# CajitaAbierta.net
KiCad netlist of a schematic drawn in EAGLE
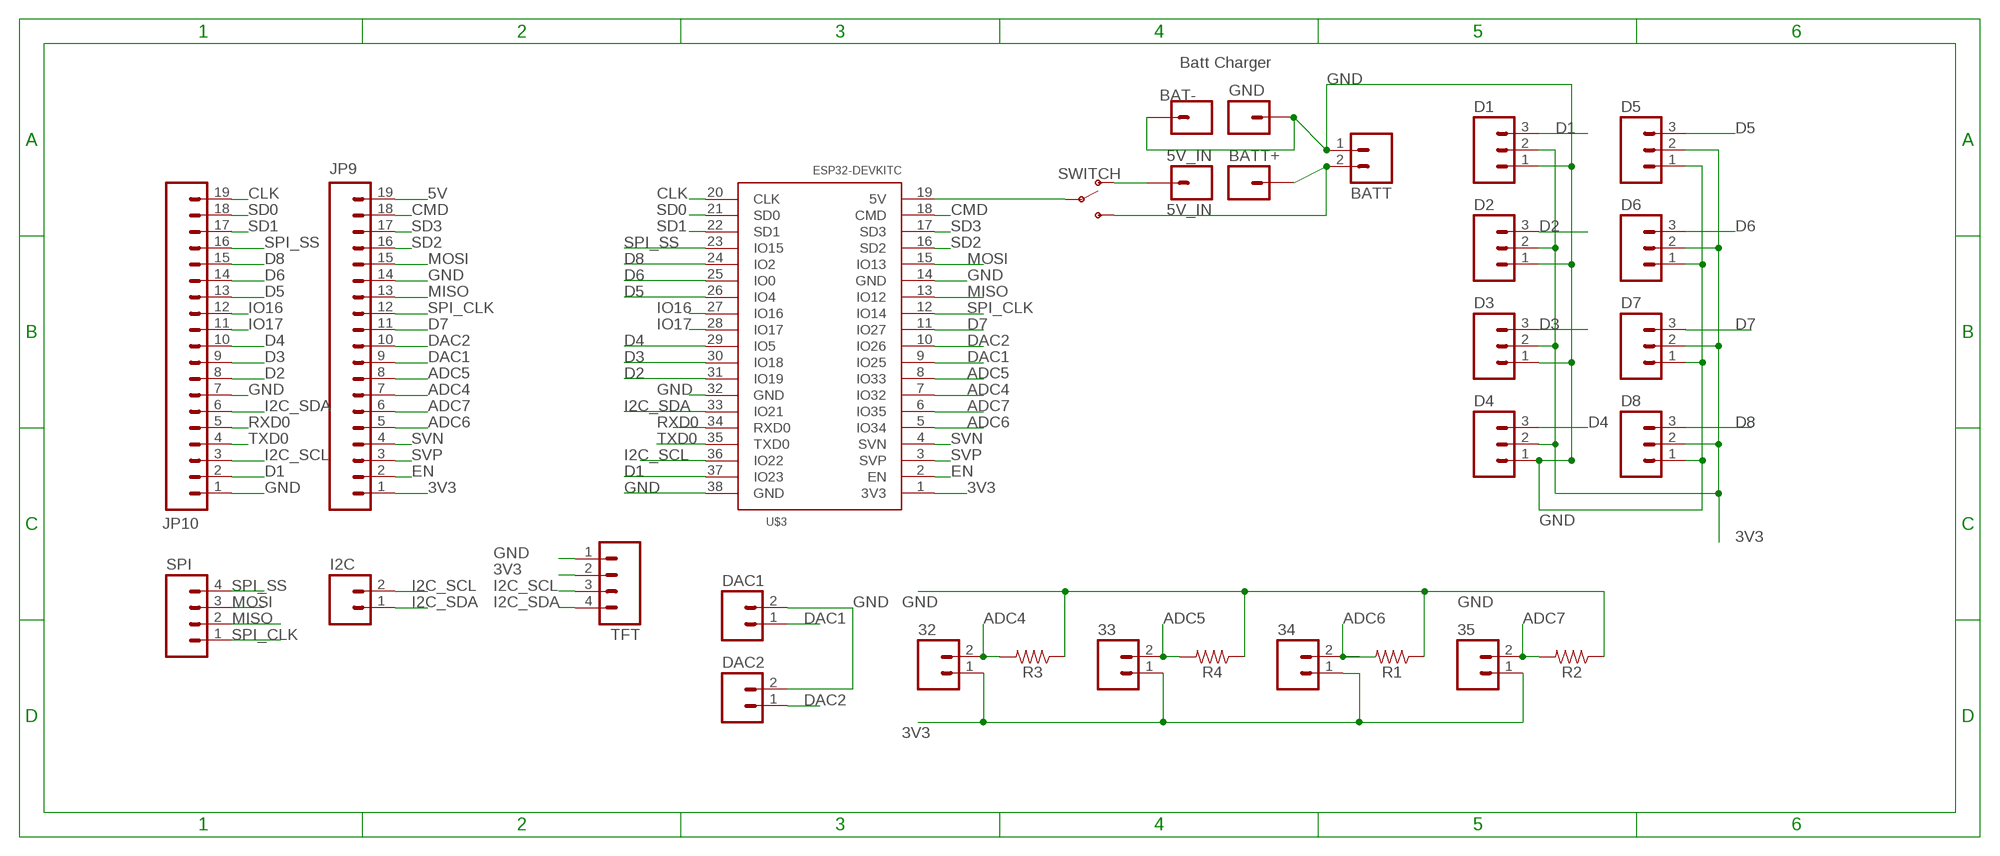
[diagram p0: schematic, sheet 1]

(export (version "E")
  (design (tool "Eeschema 10.0.6"))
  (components
    (comp (ref "5V_IN")
      (value "5V_IN")
      (footprint "eagle-import:1X01")
      (libsource (lib "eagle-import") (part "M01PTH"))
    )
    (comp (ref "32")
      (value "M02PTH")
      (footprint "eagle-import:1X02")
      (libsource (lib "eagle-import") (part "SparkFun-Connectors_6242394_M02PTH"))
    )
    (comp (ref "33")
      (value "M02PTH")
      (footprint "eagle-import:1X02")
      (libsource (lib "eagle-import") (part "SparkFun-Connectors_6242394_M02PTH"))
    )
    (comp (ref "34")
      (value "M02PTH")
      (footprint "eagle-import:1X02")
      (libsource (lib "eagle-import") (part "SparkFun-Connectors_6242394_M02PTH"))
    )
    (comp (ref "35")
      (value "M02PTH")
      (footprint "eagle-import:1X02")
      (libsource (lib "eagle-import") (part "SparkFun-Connectors_6242394_M02PTH"))
    )
    (comp (ref "BAT-")
      (value "M01PTH")
      (footprint "eagle-import:1X01")
      (libsource (lib "eagle-import") (part "M01PTH"))
    )
    (comp (ref "BATT")
      (value "M02LOCK_LONGPADS")
      (footprint "eagle-import:1X02_LOCK_LONGPADS")
      (libsource (lib "eagle-import") (part "M02LOCK_LONGPADS"))
    )
    (comp (ref "BATT+")
      (value "M01PTH")
      (footprint "eagle-import:1X01")
      (libsource (lib "eagle-import") (part "M01PTH"))
    )
    (comp (ref "D1")
      (value "M03LOCK_LONGPADS")
      (footprint "eagle-import:1X03_LOCK_LONGPADS")
      (libsource (lib "eagle-import") (part "M03LOCK_LONGPADS"))
    )
    (comp (ref "D2")
      (value "M03LOCK_LONGPADS")
      (footprint "eagle-import:1X03_LOCK_LONGPADS")
      (libsource (lib "eagle-import") (part "M03LOCK_LONGPADS"))
    )
    (comp (ref "D3")
      (value "M03LOCK_LONGPADS")
      (footprint "eagle-import:1X03_LOCK_LONGPADS")
      (libsource (lib "eagle-import") (part "M03LOCK_LONGPADS"))
    )
    (comp (ref "D4")
      (value "M03LOCK_LONGPADS")
      (footprint "eagle-import:1X03_LOCK_LONGPADS")
      (libsource (lib "eagle-import") (part "M03LOCK_LONGPADS"))
    )
    (comp (ref "D5")
      (value "M03LOCK_LONGPADS")
      (footprint "eagle-import:1X03_LOCK_LONGPADS")
      (libsource (lib "eagle-import") (part "M03LOCK_LONGPADS"))
    )
    (comp (ref "D6")
      (value "M03LOCK_LONGPADS")
      (footprint "eagle-import:1X03_LOCK_LONGPADS")
      (libsource (lib "eagle-import") (part "M03LOCK_LONGPADS"))
    )
    (comp (ref "D7")
      (value "M03LOCK_LONGPADS")
      (footprint "eagle-import:1X03_LOCK_LONGPADS")
      (libsource (lib "eagle-import") (part "M03LOCK_LONGPADS"))
    )
    (comp (ref "D8")
      (value "M03LOCK_LONGPADS")
      (footprint "eagle-import:1X03_LOCK_LONGPADS")
      (libsource (lib "eagle-import") (part "M03LOCK_LONGPADS"))
    )
    (comp (ref "DAC1")
      (value "M02PTH")
      (footprint "eagle-import:1X02")
      (libsource (lib "eagle-import") (part "SparkFun-Connectors_6242394_M02PTH"))
    )
    (comp (ref "DAC2")
      (value "M02PTH")
      (footprint "eagle-import:1X02")
      (libsource (lib "eagle-import") (part "SparkFun-Connectors_6242394_M02PTH"))
    )
    (comp (ref "GND")
      (value "Batt Charger")
      (footprint "eagle-import:1X01")
      (libsource (lib "eagle-import") (part "M01PTH"))
    )
    (comp (ref "I2C")
      (value "M02PTH")
      (footprint "eagle-import:1X02")
      (libsource (lib "eagle-import") (part "SparkFun-Connectors_6242394_M02PTH"))
    )
    (comp (ref "JP9")
      (value "M191X19")
      (footprint "eagle-import:1X19")
      (libsource (lib "eagle-import") (part "M191X19"))
    )
    (comp (ref "JP10")
      (value "M191X19")
      (footprint "eagle-import:1X19")
      (libsource (lib "eagle-import") (part "M191X19"))
    )
    (comp (ref "R1")
      (value "RESISTOR1206")
      (footprint "eagle-import:1206")
      (libsource (lib "eagle-import") (part "RESISTOR1206"))
    )
    (comp (ref "R2")
      (value "RESISTOR1206")
      (footprint "eagle-import:1206")
      (libsource (lib "eagle-import") (part "RESISTOR1206"))
    )
    (comp (ref "R3")
      (value "RESISTOR1206")
      (footprint "eagle-import:1206")
      (libsource (lib "eagle-import") (part "RESISTOR1206"))
    )
    (comp (ref "R4")
      (value "RESISTOR1206")
      (footprint "eagle-import:1206")
      (libsource (lib "eagle-import") (part "RESISTOR1206"))
    )
    (comp (ref "SPI")
      (value "M04PTH")
      (footprint "eagle-import:1X04")
      (libsource (lib "eagle-import") (part "M04PTH"))
    )
    (comp (ref "SWITCH")
      (value "SWITCH-SPDT-SMD-RIGHT-ANGLE")
      (footprint "eagle-import:SWITCH_SPST_SMD_A")
      (libsource (lib "eagle-import") (part "SWITCH-SPDT-SMD-RIGHT-ANGLE"))
    )
    (comp (ref "TFT")
      (value "M04PTH")
      (footprint "eagle-import:1X04")
      (libsource (lib "eagle-import") (part "M04PTH"))
    )
    (comp (ref "U$3")
      (value "ESP32DEVKITC")
      (footprint "eagle-import:ESP32-DEVKITC")
      (libsource (lib "eagle-import") (part "ESP32DEVKITC"))
    )
  )
  (nets
    (net (code "1") (name "/3V3") (class "Default")
      (node (ref "32") (pin "1") (pinfunction "1_1") (pintype "passive"))
      (node (ref "33") (pin "1") (pinfunction "1_1") (pintype "passive"))
      (node (ref "34") (pin "1") (pinfunction "1_1") (pintype "passive"))
      (node (ref "35") (pin "1") (pinfunction "1_1") (pintype "passive"))
      (node (ref "D1") (pin "2") (pinfunction "2_2") (pintype "passive"))
      (node (ref "D2") (pin "2") (pinfunction "2_2") (pintype "passive"))
      (node (ref "D3") (pin "2") (pinfunction "2_2") (pintype "passive"))
      (node (ref "D4") (pin "2") (pinfunction "2_2") (pintype "passive"))
      (node (ref "D5") (pin "2") (pinfunction "2_2") (pintype "passive"))
      (node (ref "D6") (pin "2") (pinfunction "2_2") (pintype "passive"))
      (node (ref "D7") (pin "2") (pinfunction "2_2") (pintype "passive"))
      (node (ref "D8") (pin "2") (pinfunction "2_2") (pintype "passive"))
      (node (ref "JP9") (pin "1") (pinfunction "1_1") (pintype "passive"))
      (node (ref "TFT") (pin "2") (pinfunction "2_2") (pintype "passive"))
      (node (ref "U$3") (pin "1") (pinfunction "3V3_1") (pintype "bidirectional"))
    )
    (net (code "2") (name "/5V") (class "Default")
      (node (ref "JP9") (pin "19") (pinfunction "19_19") (pintype "passive"))
      (node (ref "SWITCH") (pin "2") (pinfunction "P_2") (pintype "passive"))
      (node (ref "U$3") (pin "19") (pinfunction "5V_19") (pintype "bidirectional"))
    )
    (net (code "3") (name "/ADC4") (class "Default")
      (node (ref "32") (pin "2") (pinfunction "2_2") (pintype "passive"))
      (node (ref "JP9") (pin "7") (pinfunction "7_7") (pintype "passive"))
      (node (ref "R3") (pin "2") (pinfunction "2_2") (pintype "passive"))
      (node (ref "U$3") (pin "7") (pinfunction "IO32_7") (pintype "bidirectional"))
    )
    (net (code "4") (name "/ADC5") (class "Default")
      (node (ref "33") (pin "2") (pinfunction "2_2") (pintype "passive"))
      (node (ref "JP9") (pin "8") (pinfunction "8_8") (pintype "passive"))
      (node (ref "R4") (pin "2") (pinfunction "2_2") (pintype "passive"))
      (node (ref "U$3") (pin "8") (pinfunction "IO33_8") (pintype "bidirectional"))
    )
    (net (code "5") (name "/ADC6") (class "Default")
      (node (ref "34") (pin "2") (pinfunction "2_2") (pintype "passive"))
      (node (ref "JP9") (pin "5") (pinfunction "5_5") (pintype "passive"))
      (node (ref "R1") (pin "2") (pinfunction "2_2") (pintype "passive"))
      (node (ref "U$3") (pin "5") (pinfunction "IO34_5") (pintype "bidirectional"))
    )
    (net (code "6") (name "/ADC7") (class "Default")
      (node (ref "35") (pin "2") (pinfunction "2_2") (pintype "passive"))
      (node (ref "JP9") (pin "6") (pinfunction "6_6") (pintype "passive"))
      (node (ref "R2") (pin "2") (pinfunction "2_2") (pintype "passive"))
      (node (ref "U$3") (pin "6") (pinfunction "IO35_6") (pintype "bidirectional"))
    )
    (net (code "7") (name "/CLK") (class "Default")
      (node (ref "JP10") (pin "19") (pinfunction "19_19") (pintype "passive"))
      (node (ref "U$3") (pin "20") (pinfunction "CLK_20") (pintype "bidirectional"))
    )
    (net (code "8") (name "/CMD") (class "Default")
      (node (ref "JP9") (pin "18") (pinfunction "18_18") (pintype "passive"))
      (node (ref "U$3") (pin "18") (pinfunction "CMD_18") (pintype "bidirectional"))
    )
    (net (code "9") (name "/D1") (class "Default")
      (node (ref "D1") (pin "3") (pinfunction "3_3") (pintype "passive"))
      (node (ref "JP10") (pin "2") (pinfunction "2_2") (pintype "passive"))
      (node (ref "U$3") (pin "37") (pinfunction "IO23_37") (pintype "bidirectional"))
    )
    (net (code "10") (name "/D2") (class "Default")
      (node (ref "D2") (pin "3") (pinfunction "3_3") (pintype "passive"))
      (node (ref "JP10") (pin "8") (pinfunction "8_8") (pintype "passive"))
      (node (ref "U$3") (pin "31") (pinfunction "IO19_31") (pintype "bidirectional"))
    )
    (net (code "11") (name "/D3") (class "Default")
      (node (ref "D3") (pin "3") (pinfunction "3_3") (pintype "passive"))
      (node (ref "JP10") (pin "9") (pinfunction "9_9") (pintype "passive"))
      (node (ref "U$3") (pin "30") (pinfunction "IO18_30") (pintype "bidirectional"))
    )
    (net (code "12") (name "/D4") (class "Default")
      (node (ref "D4") (pin "3") (pinfunction "3_3") (pintype "passive"))
      (node (ref "JP10") (pin "10") (pinfunction "10_10") (pintype "passive"))
      (node (ref "U$3") (pin "29") (pinfunction "IO5_29") (pintype "bidirectional"))
    )
    (net (code "13") (name "/D5") (class "Default")
      (node (ref "D5") (pin "3") (pinfunction "3_3") (pintype "passive"))
      (node (ref "JP10") (pin "13") (pinfunction "13_13") (pintype "passive"))
      (node (ref "U$3") (pin "26") (pinfunction "IO4_26") (pintype "bidirectional"))
    )
    (net (code "14") (name "/D6") (class "Default")
      (node (ref "D6") (pin "3") (pinfunction "3_3") (pintype "passive"))
      (node (ref "JP10") (pin "14") (pinfunction "14_14") (pintype "passive"))
      (node (ref "U$3") (pin "25") (pinfunction "IO0_25") (pintype "bidirectional"))
    )
    (net (code "15") (name "/D7") (class "Default")
      (node (ref "D7") (pin "3") (pinfunction "3_3") (pintype "passive"))
      (node (ref "JP9") (pin "11") (pinfunction "11_11") (pintype "passive"))
      (node (ref "U$3") (pin "11") (pinfunction "IO27_11") (pintype "bidirectional"))
    )
    (net (code "16") (name "/D8") (class "Default")
      (node (ref "D8") (pin "3") (pinfunction "3_3") (pintype "passive"))
      (node (ref "JP10") (pin "15") (pinfunction "15_15") (pintype "passive"))
      (node (ref "U$3") (pin "24") (pinfunction "IO2_24") (pintype "bidirectional"))
    )
    (net (code "17") (name "/DAC1") (class "Default")
      (node (ref "DAC1") (pin "1") (pinfunction "1_1") (pintype "passive"))
      (node (ref "JP9") (pin "9") (pinfunction "9_9") (pintype "passive"))
      (node (ref "U$3") (pin "9") (pinfunction "IO25_9") (pintype "bidirectional"))
    )
    (net (code "18") (name "/DAC2") (class "Default")
      (node (ref "DAC2") (pin "1") (pinfunction "1_1") (pintype "passive"))
      (node (ref "JP9") (pin "10") (pinfunction "10_10") (pintype "passive"))
      (node (ref "U$3") (pin "10") (pinfunction "IO26_10") (pintype "bidirectional"))
    )
    (net (code "19") (name "/EN") (class "Default")
      (node (ref "JP9") (pin "2") (pinfunction "2_2") (pintype "passive"))
      (node (ref "U$3") (pin "2") (pinfunction "EN_2") (pintype "bidirectional"))
    )
    (net (code "20") (name "/GND") (class "Default")
      (node (ref "BAT-") (pin "1") (pinfunction "1_1") (pintype "passive"))
      (node (ref "BATT") (pin "1") (pinfunction "1_1") (pintype "passive"))
      (node (ref "D1") (pin "1") (pinfunction "1_1") (pintype "passive"))
      (node (ref "D2") (pin "1") (pinfunction "1_1") (pintype "passive"))
      (node (ref "D3") (pin "1") (pinfunction "1_1") (pintype "passive"))
      (node (ref "D4") (pin "1") (pinfunction "1_1") (pintype "passive"))
      (node (ref "D5") (pin "1") (pinfunction "1_1") (pintype "passive"))
      (node (ref "D6") (pin "1") (pinfunction "1_1") (pintype "passive"))
      (node (ref "D7") (pin "1") (pinfunction "1_1") (pintype "passive"))
      (node (ref "D8") (pin "1") (pinfunction "1_1") (pintype "passive"))
      (node (ref "DAC1") (pin "2") (pinfunction "2_2") (pintype "passive"))
      (node (ref "DAC2") (pin "2") (pinfunction "2_2") (pintype "passive"))
      (node (ref "GND") (pin "1") (pinfunction "1_1") (pintype "passive"))
      (node (ref "JP10") (pin "1") (pinfunction "1_1") (pintype "passive"))
      (node (ref "JP10") (pin "7") (pinfunction "7_7") (pintype "passive"))
      (node (ref "JP9") (pin "14") (pinfunction "14_14") (pintype "passive"))
      (node (ref "R1") (pin "1") (pinfunction "1_1") (pintype "passive"))
      (node (ref "R2") (pin "1") (pinfunction "1_1") (pintype "passive"))
      (node (ref "R3") (pin "1") (pinfunction "1_1") (pintype "passive"))
      (node (ref "R4") (pin "1") (pinfunction "1_1") (pintype "passive"))
      (node (ref "TFT") (pin "1") (pinfunction "1_1") (pintype "passive"))
      (node (ref "U$3") (pin "14") (pinfunction "GND_14") (pintype "bidirectional"))
      (node (ref "U$3") (pin "32") (pinfunction "GND_32") (pintype "bidirectional"))
      (node (ref "U$3") (pin "38") (pinfunction "GND_38") (pintype "bidirectional"))
    )
    (net (code "21") (name "/I2C_SCL") (class "Default")
      (node (ref "I2C") (pin "2") (pinfunction "2_2") (pintype "passive"))
      (node (ref "JP10") (pin "3") (pinfunction "3_3") (pintype "passive"))
      (node (ref "TFT") (pin "3") (pinfunction "3_3") (pintype "passive"))
      (node (ref "U$3") (pin "36") (pinfunction "IO22_36") (pintype "bidirectional"))
    )
    (net (code "22") (name "/I2C_SDA") (class "Default")
      (node (ref "I2C") (pin "1") (pinfunction "1_1") (pintype "passive"))
      (node (ref "JP10") (pin "6") (pinfunction "6_6") (pintype "passive"))
      (node (ref "TFT") (pin "4") (pinfunction "4_4") (pintype "passive"))
      (node (ref "U$3") (pin "33") (pinfunction "IO21_33") (pintype "bidirectional"))
    )
    (net (code "23") (name "/IO16") (class "Default")
      (node (ref "JP10") (pin "12") (pinfunction "12_12") (pintype "passive"))
      (node (ref "U$3") (pin "27") (pinfunction "IO16_27") (pintype "bidirectional"))
    )
    (net (code "24") (name "/IO17") (class "Default")
      (node (ref "JP10") (pin "11") (pinfunction "11_11") (pintype "passive"))
      (node (ref "U$3") (pin "28") (pinfunction "IO17_28") (pintype "bidirectional"))
    )
    (net (code "25") (name "/MISO") (class "Default")
      (node (ref "JP9") (pin "13") (pinfunction "13_13") (pintype "passive"))
      (node (ref "SPI") (pin "2") (pinfunction "2_2") (pintype "passive"))
      (node (ref "U$3") (pin "13") (pinfunction "IO12_13") (pintype "bidirectional"))
    )
    (net (code "26") (name "/MOSI") (class "Default")
      (node (ref "JP9") (pin "15") (pinfunction "15_15") (pintype "passive"))
      (node (ref "SPI") (pin "3") (pinfunction "3_3") (pintype "passive"))
      (node (ref "U$3") (pin "15") (pinfunction "IO13_15") (pintype "bidirectional"))
    )
    (net (code "27") (name "/RXD0") (class "Default")
      (node (ref "JP10") (pin "5") (pinfunction "5_5") (pintype "passive"))
      (node (ref "U$3") (pin "34") (pinfunction "RXD0_34") (pintype "bidirectional"))
    )
    (net (code "28") (name "/SD0") (class "Default")
      (node (ref "JP10") (pin "18") (pinfunction "18_18") (pintype "passive"))
      (node (ref "U$3") (pin "21") (pinfunction "SD0_21") (pintype "bidirectional"))
    )
    (net (code "29") (name "/SD1") (class "Default")
      (node (ref "JP10") (pin "17") (pinfunction "17_17") (pintype "passive"))
      (node (ref "U$3") (pin "22") (pinfunction "SD1_22") (pintype "bidirectional"))
    )
    (net (code "30") (name "/SD2") (class "Default")
      (node (ref "JP9") (pin "16") (pinfunction "16_16") (pintype "passive"))
      (node (ref "U$3") (pin "16") (pinfunction "SD2_16") (pintype "bidirectional"))
    )
    (net (code "31") (name "/SD3") (class "Default")
      (node (ref "JP9") (pin "17") (pinfunction "17_17") (pintype "passive"))
      (node (ref "U$3") (pin "17") (pinfunction "SD3_17") (pintype "bidirectional"))
    )
    (net (code "32") (name "/SPI_CLK") (class "Default")
      (node (ref "JP9") (pin "12") (pinfunction "12_12") (pintype "passive"))
      (node (ref "SPI") (pin "1") (pinfunction "1_1") (pintype "passive"))
      (node (ref "U$3") (pin "12") (pinfunction "IO14_12") (pintype "bidirectional"))
    )
    (net (code "33") (name "/SPI_SS") (class "Default")
      (node (ref "JP10") (pin "16") (pinfunction "16_16") (pintype "passive"))
      (node (ref "SPI") (pin "4") (pinfunction "4_4") (pintype "passive"))
      (node (ref "U$3") (pin "23") (pinfunction "IO15_23") (pintype "bidirectional"))
    )
    (net (code "34") (name "/SVN") (class "Default")
      (node (ref "JP9") (pin "4") (pinfunction "4_4") (pintype "passive"))
      (node (ref "U$3") (pin "4") (pinfunction "SVN_4") (pintype "bidirectional"))
    )
    (net (code "35") (name "/SVP") (class "Default")
      (node (ref "JP9") (pin "3") (pinfunction "3_3") (pintype "passive"))
      (node (ref "U$3") (pin "3") (pinfunction "SVP_3") (pintype "bidirectional"))
    )
    (net (code "36") (name "/TXD0") (class "Default")
      (node (ref "JP10") (pin "4") (pinfunction "4_4") (pintype "passive"))
      (node (ref "U$3") (pin "35") (pinfunction "TXD0_35") (pintype "bidirectional"))
    )
    (net (code "37") (name "Net-(SWITCH-O)") (class "Default")
      (node (ref "5V_IN") (pin "1") (pinfunction "1_1") (pintype "passive"))
      (node (ref "SWITCH") (pin "1") (pinfunction "O_1") (pintype "passive"))
    )
    (net (code "38") (name "Net-(SWITCH-S)") (class "Default")
      (node (ref "BATT") (pin "2") (pinfunction "2_2") (pintype "passive"))
      (node (ref "BATT+") (pin "1") (pinfunction "1_1") (pintype "passive"))
      (node (ref "SWITCH") (pin "3") (pinfunction "S_3") (pintype "passive"))
    )
  )
)
